# hdd-booster.net
KiCad netlist of a schematic drawn in EAGLE
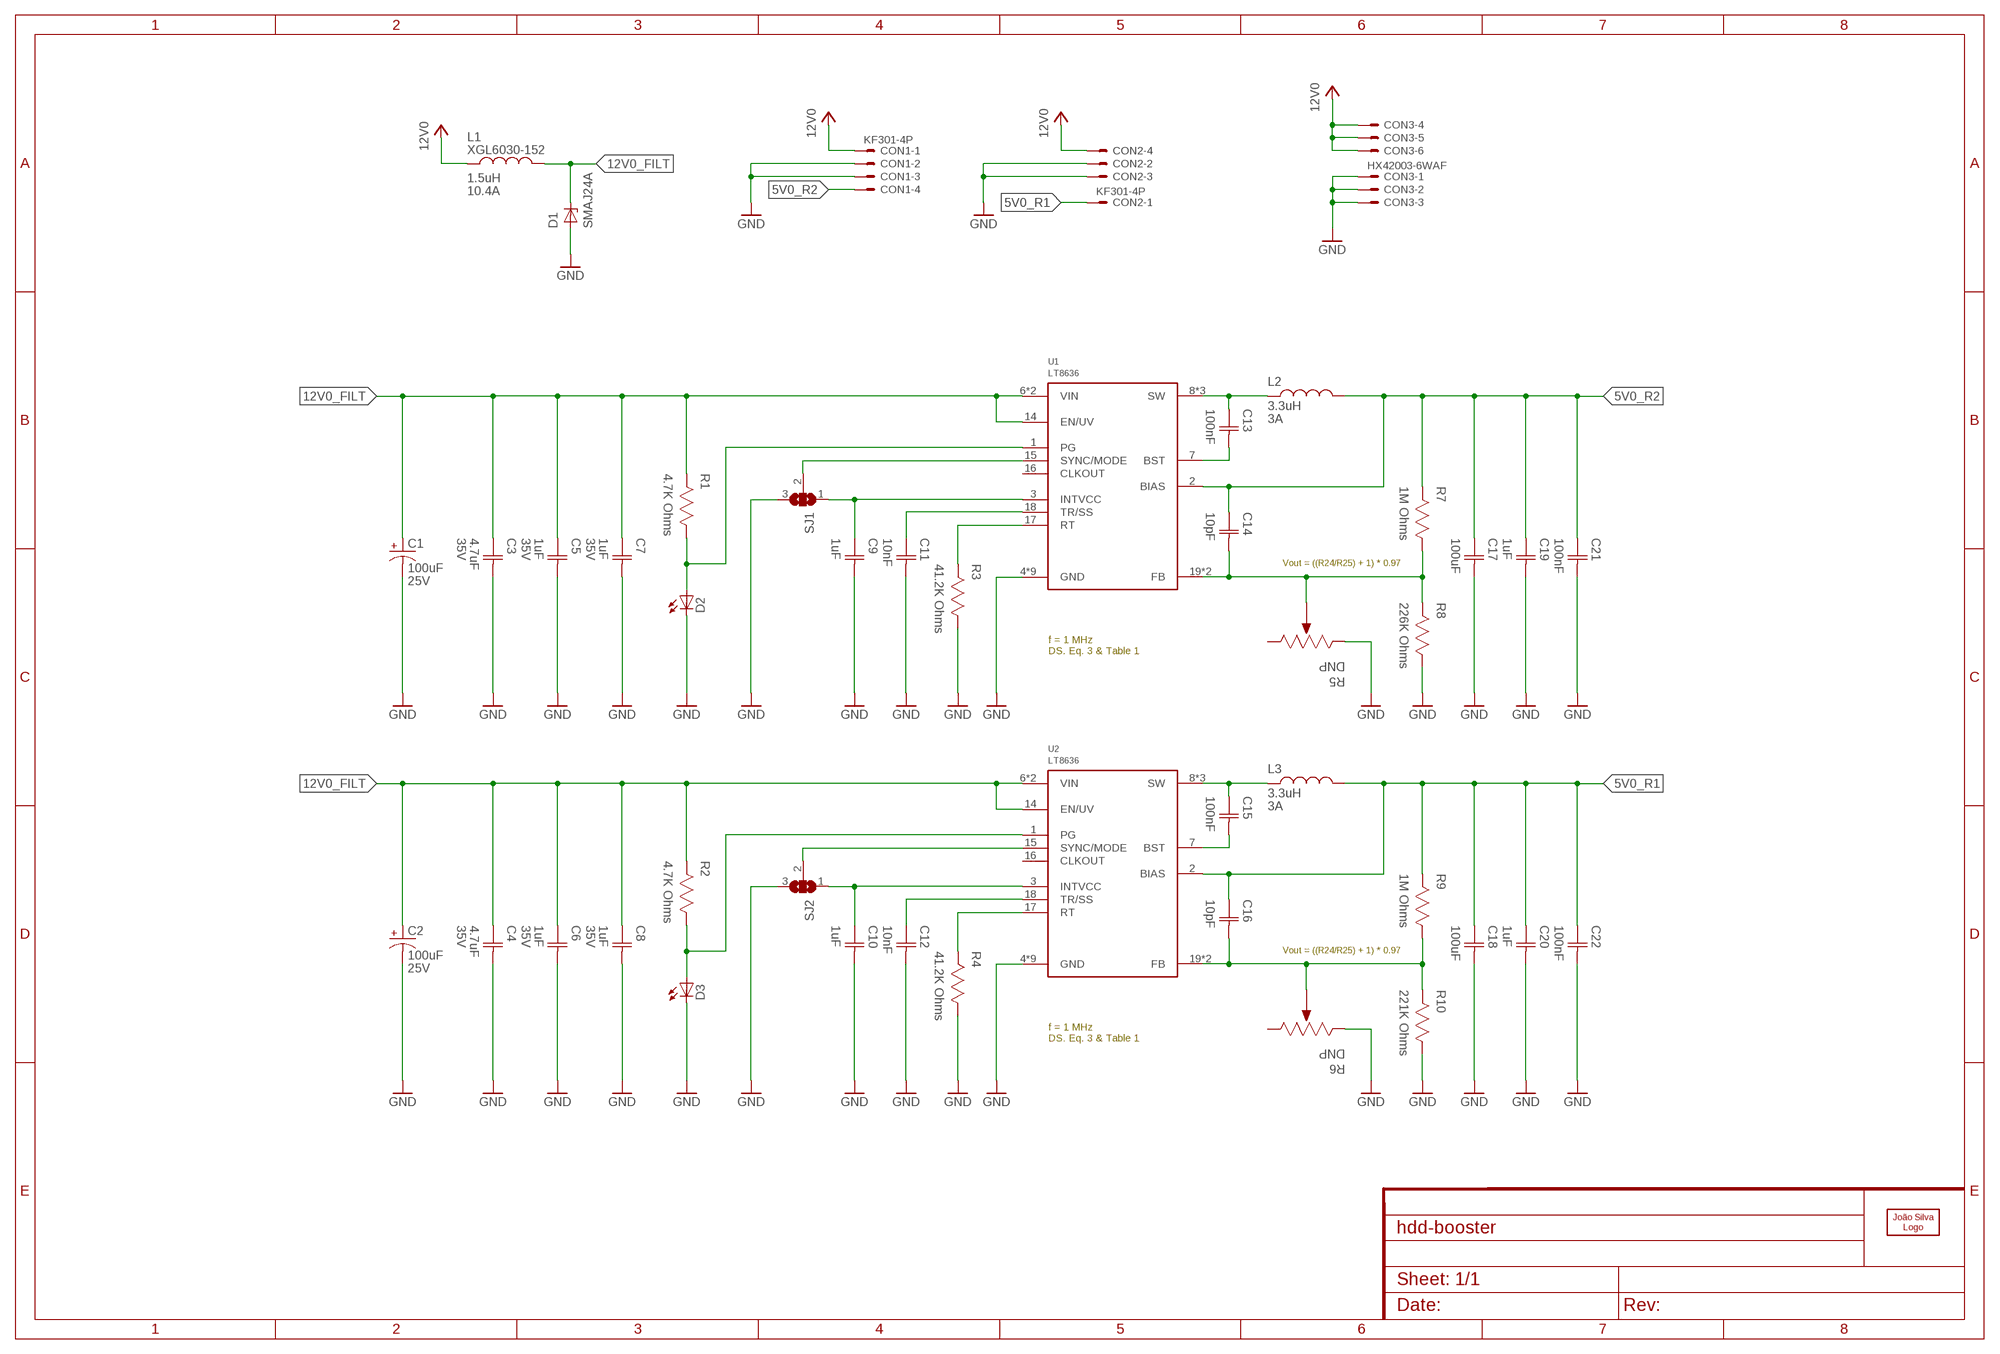
[diagram p0: schematic, sheet 1]

(export (version "E")
  (design (tool "Eeschema 10.0.6"))
  (components
    (comp (ref "C1")
      (value "100uF")
      (footprint "eagle-import:AL-CAP-CASE-D")
      (fields (field (name "VOLTAGE") "25V"))
      (libsource (lib "eagle-import") (part "ALUMINIUM-CAPACITOR-CASE-D"))
    )
    (comp (ref "C2")
      (value "100uF")
      (footprint "eagle-import:AL-CAP-CASE-D")
      (fields (field (name "VOLTAGE") "25V"))
      (libsource (lib "eagle-import") (part "ALUMINIUM-CAPACITOR-CASE-D"))
    )
    (comp (ref "C3")
      (value "4.7uF")
      (footprint "eagle-import:CAP0603")
      (fields (field (name "VOLTAGE") "35V"))
      (libsource (lib "eagle-import") (part "CAPACITOR-0603"))
    )
    (comp (ref "C4")
      (value "4.7uF")
      (footprint "eagle-import:CAP0603")
      (fields (field (name "VOLTAGE") "35V"))
      (libsource (lib "eagle-import") (part "CAPACITOR-0603"))
    )
    (comp (ref "C5")
      (value "1uF")
      (footprint "eagle-import:CAP0402")
      (fields (field (name "VOLTAGE") "35V"))
      (libsource (lib "eagle-import") (part "CAPACITOR-0402"))
    )
    (comp (ref "C6")
      (value "1uF")
      (footprint "eagle-import:CAP0402")
      (fields (field (name "VOLTAGE") "35V"))
      (libsource (lib "eagle-import") (part "CAPACITOR-0402"))
    )
    (comp (ref "C7")
      (value "1uF")
      (footprint "eagle-import:CAP0402")
      (fields (field (name "VOLTAGE") "35V"))
      (libsource (lib "eagle-import") (part "CAPACITOR-0402"))
    )
    (comp (ref "C8")
      (value "1uF")
      (footprint "eagle-import:CAP0402")
      (fields (field (name "VOLTAGE") "35V"))
      (libsource (lib "eagle-import") (part "CAPACITOR-0402"))
    )
    (comp (ref "C9")
      (value "1uF")
      (footprint "eagle-import:CAP0402")
      (libsource (lib "eagle-import") (part "CAPACITOR-0402"))
    )
    (comp (ref "C10")
      (value "1uF")
      (footprint "eagle-import:CAP0402")
      (libsource (lib "eagle-import") (part "CAPACITOR-0402"))
    )
    (comp (ref "C11")
      (value "10nF")
      (footprint "eagle-import:CAP0402")
      (libsource (lib "eagle-import") (part "CAPACITOR-0402"))
    )
    (comp (ref "C12")
      (value "10nF")
      (footprint "eagle-import:CAP0402")
      (libsource (lib "eagle-import") (part "CAPACITOR-0402"))
    )
    (comp (ref "C13")
      (value "100nF")
      (footprint "eagle-import:CAP0402")
      (libsource (lib "eagle-import") (part "CAPACITOR-0402"))
    )
    (comp (ref "C14")
      (value "10pF")
      (footprint "eagle-import:CAP0402")
      (libsource (lib "eagle-import") (part "CAPACITOR-0402"))
    )
    (comp (ref "C15")
      (value "100nF")
      (footprint "eagle-import:CAP0402")
      (libsource (lib "eagle-import") (part "CAPACITOR-0402"))
    )
    (comp (ref "C16")
      (value "10pF")
      (footprint "eagle-import:CAP0402")
      (libsource (lib "eagle-import") (part "CAPACITOR-0402"))
    )
    (comp (ref "C17")
      (value "100uF")
      (footprint "eagle-import:CAP1206")
      (libsource (lib "eagle-import") (part "CAPACITOR-1206"))
    )
    (comp (ref "C18")
      (value "100uF")
      (footprint "eagle-import:CAP1206")
      (libsource (lib "eagle-import") (part "CAPACITOR-1206"))
    )
    (comp (ref "C19")
      (value "1uF")
      (footprint "eagle-import:CAP0402")
      (libsource (lib "eagle-import") (part "CAPACITOR-0402"))
    )
    (comp (ref "C20")
      (value "1uF")
      (footprint "eagle-import:CAP0402")
      (libsource (lib "eagle-import") (part "CAPACITOR-0402"))
    )
    (comp (ref "C21")
      (value "100nF")
      (footprint "eagle-import:CAP0402")
      (libsource (lib "eagle-import") (part "CAPACITOR-0402"))
    )
    (comp (ref "C22")
      (value "100nF")
      (footprint "eagle-import:CAP0402")
      (libsource (lib "eagle-import") (part "CAPACITOR-0402"))
    )
    (comp (ref "CON1")
      (value "KF301-4P")
      (footprint "eagle-import:KF301-4P")
      (libsource (lib "eagle-import") (part "KF301-4P"))
    )
    (comp (ref "CON2")
      (value "KF301-4P")
      (footprint "eagle-import:KF301-4P")
      (libsource (lib "eagle-import") (part "KF301-4P"))
    )
    (comp (ref "CON3")
      (value "HX42003-6WAF")
      (footprint "eagle-import:HX42003-6WAF")
      (libsource (lib "eagle-import") (part "HX42003-6WAF"))
    )
    (comp (ref "D1")
      (value "SMAJ24A")
      (footprint "eagle-import:DO214AC")
      (fields (field (name "MF") "Littelfuse"))
      (libsource (lib "eagle-import") (part "SMAJA24"))
    )
    (comp (ref "D2")
      (value "LED1206")
      (footprint "eagle-import:1206")
      (libsource (lib "eagle-import") (part "LED1206"))
    )
    (comp (ref "D3")
      (value "LED1206")
      (footprint "eagle-import:1206")
      (libsource (lib "eagle-import") (part "LED1206"))
    )
    (comp (ref "L1")
      (value "1.5uH")
      (footprint "eagle-import:XGL6030")
      (fields (field (name "CURRENT") "10.4A") (field (name "REF") "XGL6030-152"))
      (libsource (lib "eagle-import") (part "XGL6030-152"))
    )
    (comp (ref "L2")
      (value "3.3uH")
      (footprint "eagle-import:XGL6030")
      (fields (field (name "CURRENT") "7.6A") (field (name "CURRENT_1") "3A"))
      (libsource (lib "eagle-import") (part "XGL6030-332"))
    )
    (comp (ref "L3")
      (value "3.3uH")
      (footprint "eagle-import:XGL6030")
      (fields (field (name "CURRENT") "7.6A") (field (name "CURRENT_1") "3A"))
      (libsource (lib "eagle-import") (part "XGL6030-332"))
    )
    (comp (ref "LOGO1")
      (value "JSILVA-5MM")
      (footprint "eagle-import:JSILVA_5MM")
      (libsource (lib "eagle-import") (part "JSILVA-5MM"))
    )
    (comp (ref "R1")
      (value "4.7K Ohms")
      (footprint "eagle-import:RES0402")
      (libsource (lib "eagle-import") (part "RESISTOR-0402"))
    )
    (comp (ref "R2")
      (value "4.7K Ohms")
      (footprint "eagle-import:RES0402")
      (libsource (lib "eagle-import") (part "RESISTOR-0402"))
    )
    (comp (ref "R3")
      (value "41.2K Ohms")
      (footprint "eagle-import:RES0402")
      (libsource (lib "eagle-import") (part "RESISTOR-0402"))
    )
    (comp (ref "R4")
      (value "41.2K Ohms")
      (footprint "eagle-import:RES0402")
      (libsource (lib "eagle-import") (part "RESISTOR-0402"))
    )
    (comp (ref "R5")
      (value "DNP")
      (footprint "eagle-import:POT3MM")
      (libsource (lib "eagle-import") (part "POTENTIOMETER-SMD-3X3"))
    )
    (comp (ref "R6")
      (value "DNP")
      (footprint "eagle-import:POT3MM")
      (libsource (lib "eagle-import") (part "POTENTIOMETER-SMD-3X3"))
    )
    (comp (ref "R7")
      (value "1M Ohms")
      (footprint "eagle-import:RES0402")
      (libsource (lib "eagle-import") (part "RESISTOR-0402"))
    )
    (comp (ref "R8")
      (value "226K Ohms")
      (footprint "eagle-import:RES0402")
      (libsource (lib "eagle-import") (part "RESISTOR-0402"))
    )
    (comp (ref "R9")
      (value "1M Ohms")
      (footprint "eagle-import:RES0402")
      (libsource (lib "eagle-import") (part "RESISTOR-0402"))
    )
    (comp (ref "R10")
      (value "221K Ohms")
      (footprint "eagle-import:RES0402")
      (libsource (lib "eagle-import") (part "RESISTOR-0402"))
    )
    (comp (ref "SJ1")
      (value "SJ2S")
      (footprint "eagle-import:SJ2_S")
      (libsource (lib "eagle-import") (part "SJ2S"))
    )
    (comp (ref "SJ2")
      (value "SJ2S")
      (footprint "eagle-import:SJ2_S")
      (libsource (lib "eagle-import") (part "SJ2S"))
    )
    (comp (ref "U1")
      (value "LT8636")
      (footprint "eagle-import:QFN20_ASYM_3X4_CORNER")
      (libsource (lib "eagle-import") (part "LT8636"))
    )
    (comp (ref "U2")
      (value "LT8636")
      (footprint "eagle-import:QFN20_ASYM_3X4_CORNER")
      (libsource (lib "eagle-import") (part "LT8636"))
    )
  )
  (nets
    (net (code "1") (name "5V0_R1") (class "Default")
      (node (ref "C16") (pin "1") (pinfunction "C1_1") (pintype "passive"))
      (node (ref "C18") (pin "1") (pinfunction "C1_1") (pintype "passive"))
      (node (ref "C20") (pin "1") (pinfunction "C1_1") (pintype "passive"))
      (node (ref "C22") (pin "1") (pinfunction "C1_1") (pintype "passive"))
      (node (ref "CON2") (pin "1") (pinfunction "S_1") (pintype "passive"))
      (node (ref "L3") (pin "2") (pinfunction "2_2") (pintype "passive"))
      (node (ref "R9") (pin "2") (pinfunction "2_2") (pintype "passive"))
      (node (ref "U2") (pin "2") (pinfunction "BIAS_2") (pintype "bidirectional"))
    )
    (net (code "2") (name "5V0_R2") (class "Default")
      (node (ref "C14") (pin "1") (pinfunction "C1_1") (pintype "passive"))
      (node (ref "C17") (pin "1") (pinfunction "C1_1") (pintype "passive"))
      (node (ref "C19") (pin "1") (pinfunction "C1_1") (pintype "passive"))
      (node (ref "C21") (pin "1") (pinfunction "C1_1") (pintype "passive"))
      (node (ref "CON1") (pin "4") (pinfunction "S_4") (pintype "passive"))
      (node (ref "L2") (pin "2") (pinfunction "2_2") (pintype "passive"))
      (node (ref "R7") (pin "2") (pinfunction "2_2") (pintype "passive"))
      (node (ref "U1") (pin "2") (pinfunction "BIAS_2") (pintype "bidirectional"))
    )
    (net (code "3") (name "12V0") (class "Default")
      (node (ref "CON1") (pin "1") (pinfunction "S_1") (pintype "passive"))
      (node (ref "CON2") (pin "4") (pinfunction "S_4") (pintype "passive"))
      (node (ref "CON3") (pin "4") (pinfunction "S_4") (pintype "passive"))
      (node (ref "CON3") (pin "5") (pinfunction "S_5") (pintype "passive"))
      (node (ref "CON3") (pin "6") (pinfunction "S_6") (pintype "passive"))
      (node (ref "L1") (pin "1") (pinfunction "1_1") (pintype "passive"))
    )
    (net (code "4") (name "12V0_FILT") (class "Default")
      (node (ref "C1") (pin "1") (pinfunction "+_1") (pintype "passive"))
      (node (ref "C2") (pin "1") (pinfunction "+_1") (pintype "passive"))
      (node (ref "C3") (pin "1") (pinfunction "C1_1") (pintype "passive"))
      (node (ref "C4") (pin "1") (pinfunction "C1_1") (pintype "passive"))
      (node (ref "C5") (pin "1") (pinfunction "C1_1") (pintype "passive"))
      (node (ref "C6") (pin "1") (pinfunction "C1_1") (pintype "passive"))
      (node (ref "C7") (pin "1") (pinfunction "C1_1") (pintype "passive"))
      (node (ref "C8") (pin "1") (pinfunction "C1_1") (pintype "passive"))
      (node (ref "D1") (pin "C") (pinfunction "C_C") (pintype "passive"))
      (node (ref "L1") (pin "2") (pinfunction "2_2") (pintype "passive"))
      (node (ref "R1") (pin "2") (pinfunction "2_2") (pintype "passive"))
      (node (ref "R2") (pin "2") (pinfunction "2_2") (pintype "passive"))
      (node (ref "U1") (pin "11") (pinfunction "VIN_11") (pintype "bidirectional"))
      (node (ref "U1") (pin "14") (pinfunction "EN/UV_14") (pintype "bidirectional"))
      (node (ref "U1") (pin "6") (pinfunction "VIN_6") (pintype "bidirectional"))
      (node (ref "U2") (pin "11") (pinfunction "VIN_11") (pintype "bidirectional"))
      (node (ref "U2") (pin "14") (pinfunction "EN/UV_14") (pintype "bidirectional"))
      (node (ref "U2") (pin "6") (pinfunction "VIN_6") (pintype "bidirectional"))
    )
    (net (code "5") (name "GND") (class "Default")
      (node (ref "C1") (pin "2") (pinfunction "-_2") (pintype "passive"))
      (node (ref "C10") (pin "2") (pinfunction "C2_2") (pintype "passive"))
      (node (ref "C11") (pin "2") (pinfunction "C2_2") (pintype "passive"))
      (node (ref "C12") (pin "2") (pinfunction "C2_2") (pintype "passive"))
      (node (ref "C17") (pin "2") (pinfunction "C2_2") (pintype "passive"))
      (node (ref "C18") (pin "2") (pinfunction "C2_2") (pintype "passive"))
      (node (ref "C19") (pin "2") (pinfunction "C2_2") (pintype "passive"))
      (node (ref "C2") (pin "2") (pinfunction "-_2") (pintype "passive"))
      (node (ref "C20") (pin "2") (pinfunction "C2_2") (pintype "passive"))
      (node (ref "C21") (pin "2") (pinfunction "C2_2") (pintype "passive"))
      (node (ref "C22") (pin "2") (pinfunction "C2_2") (pintype "passive"))
      (node (ref "C3") (pin "2") (pinfunction "C2_2") (pintype "passive"))
      (node (ref "C4") (pin "2") (pinfunction "C2_2") (pintype "passive"))
      (node (ref "C5") (pin "2") (pinfunction "C2_2") (pintype "passive"))
      (node (ref "C6") (pin "2") (pinfunction "C2_2") (pintype "passive"))
      (node (ref "C7") (pin "2") (pinfunction "C2_2") (pintype "passive"))
      (node (ref "C8") (pin "2") (pinfunction "C2_2") (pintype "passive"))
      (node (ref "C9") (pin "2") (pinfunction "C2_2") (pintype "passive"))
      (node (ref "CON1") (pin "2") (pinfunction "S_2") (pintype "passive"))
      (node (ref "CON1") (pin "3") (pinfunction "S_3") (pintype "passive"))
      (node (ref "CON2") (pin "2") (pinfunction "S_2") (pintype "passive"))
      (node (ref "CON2") (pin "3") (pinfunction "S_3") (pintype "passive"))
      (node (ref "CON3") (pin "1") (pinfunction "S_1") (pintype "passive"))
      (node (ref "CON3") (pin "2") (pinfunction "S_2") (pintype "passive"))
      (node (ref "CON3") (pin "3") (pinfunction "S_3") (pintype "passive"))
      (node (ref "D1") (pin "A") (pinfunction "A_A") (pintype "passive"))
      (node (ref "D2") (pin "C") (pinfunction "C_C") (pintype "passive"))
      (node (ref "D3") (pin "C") (pinfunction "C_C") (pintype "passive"))
      (node (ref "R10") (pin "1") (pinfunction "1_1") (pintype "passive"))
      (node (ref "R3") (pin "1") (pinfunction "1_1") (pintype "passive"))
      (node (ref "R4") (pin "1") (pinfunction "1_1") (pintype "passive"))
      (node (ref "R5") (pin "1") (pinfunction "CCW_1") (pintype "passive"))
      (node (ref "R6") (pin "1") (pinfunction "CCW_1") (pintype "passive"))
      (node (ref "R8") (pin "1") (pinfunction "1_1") (pintype "passive"))
      (node (ref "SJ1") (pin "3") (pinfunction "3_3") (pintype "passive"))
      (node (ref "SJ2") (pin "3") (pinfunction "3_3") (pintype "passive"))
      (node (ref "U1") (pin "12") (pinfunction "GND_12") (pintype "bidirectional"))
      (node (ref "U1") (pin "13") (pinfunction "GND_13") (pintype "bidirectional"))
      (node (ref "U1") (pin "21") (pinfunction "GND_21") (pintype "bidirectional"))
      (node (ref "U1") (pin "4") (pinfunction "GND_4") (pintype "bidirectional"))
      (node (ref "U1") (pin "5") (pinfunction "GND_5") (pintype "bidirectional"))
      (node (ref "U1") (pin "M1") (pinfunction "GND_M1") (pintype "bidirectional"))
      (node (ref "U1") (pin "M2") (pinfunction "GND_M2") (pintype "bidirectional"))
      (node (ref "U1") (pin "M3") (pinfunction "GND_M3") (pintype "bidirectional"))
      (node (ref "U1") (pin "M4") (pinfunction "GND_M4") (pintype "bidirectional"))
      (node (ref "U2") (pin "12") (pinfunction "GND_12") (pintype "bidirectional"))
      (node (ref "U2") (pin "13") (pinfunction "GND_13") (pintype "bidirectional"))
      (node (ref "U2") (pin "21") (pinfunction "GND_21") (pintype "bidirectional"))
      (node (ref "U2") (pin "4") (pinfunction "GND_4") (pintype "bidirectional"))
      (node (ref "U2") (pin "5") (pinfunction "GND_5") (pintype "bidirectional"))
      (node (ref "U2") (pin "M1") (pinfunction "GND_M1") (pintype "bidirectional"))
      (node (ref "U2") (pin "M2") (pinfunction "GND_M2") (pintype "bidirectional"))
      (node (ref "U2") (pin "M3") (pinfunction "GND_M3") (pintype "bidirectional"))
      (node (ref "U2") (pin "M4") (pinfunction "GND_M4") (pintype "bidirectional"))
    )
    (net (code "6") (name "Net-(C9-C1)") (class "Default")
      (node (ref "C9") (pin "1") (pinfunction "C1_1") (pintype "passive"))
      (node (ref "SJ1") (pin "1") (pinfunction "1_1") (pintype "passive"))
      (node (ref "U1") (pin "3") (pinfunction "INTVCC_3") (pintype "bidirectional"))
    )
    (net (code "7") (name "Net-(C10-C1)") (class "Default")
      (node (ref "C10") (pin "1") (pinfunction "C1_1") (pintype "passive"))
      (node (ref "SJ2") (pin "1") (pinfunction "1_1") (pintype "passive"))
      (node (ref "U2") (pin "3") (pinfunction "INTVCC_3") (pintype "bidirectional"))
    )
    (net (code "8") (name "Net-(C11-C1)") (class "Default")
      (node (ref "C11") (pin "1") (pinfunction "C1_1") (pintype "passive"))
      (node (ref "U1") (pin "18") (pinfunction "TR/SS_18") (pintype "bidirectional"))
    )
    (net (code "9") (name "Net-(C12-C1)") (class "Default")
      (node (ref "C12") (pin "1") (pinfunction "C1_1") (pintype "passive"))
      (node (ref "U2") (pin "18") (pinfunction "TR/SS_18") (pintype "bidirectional"))
    )
    (net (code "10") (name "Net-(C13-C1)") (class "Default")
      (node (ref "C13") (pin "1") (pinfunction "C1_1") (pintype "passive"))
      (node (ref "L2") (pin "1") (pinfunction "1_1") (pintype "passive"))
      (node (ref "U1") (pin "10") (pinfunction "SW_10") (pintype "bidirectional"))
      (node (ref "U1") (pin "8") (pinfunction "SW_8") (pintype "bidirectional"))
      (node (ref "U1") (pin "9") (pinfunction "SW_9") (pintype "bidirectional"))
    )
    (net (code "11") (name "Net-(C13-C2)") (class "Default")
      (node (ref "C13") (pin "2") (pinfunction "C2_2") (pintype "passive"))
      (node (ref "U1") (pin "7") (pinfunction "BST_7") (pintype "bidirectional"))
    )
    (net (code "12") (name "Net-(C14-C2)") (class "Default")
      (node (ref "C14") (pin "2") (pinfunction "C2_2") (pintype "passive"))
      (node (ref "R5") (pin "2") (pinfunction "WIPER_2") (pintype "passive"))
      (node (ref "R7") (pin "1") (pinfunction "1_1") (pintype "passive"))
      (node (ref "R8") (pin "2") (pinfunction "2_2") (pintype "passive"))
      (node (ref "U1") (pin "19") (pinfunction "FB_19") (pintype "bidirectional"))
      (node (ref "U1") (pin "20") (pinfunction "FB_20") (pintype "bidirectional"))
    )
    (net (code "13") (name "Net-(C15-C1)") (class "Default")
      (node (ref "C15") (pin "1") (pinfunction "C1_1") (pintype "passive"))
      (node (ref "L3") (pin "1") (pinfunction "1_1") (pintype "passive"))
      (node (ref "U2") (pin "10") (pinfunction "SW_10") (pintype "bidirectional"))
      (node (ref "U2") (pin "8") (pinfunction "SW_8") (pintype "bidirectional"))
      (node (ref "U2") (pin "9") (pinfunction "SW_9") (pintype "bidirectional"))
    )
    (net (code "14") (name "Net-(C15-C2)") (class "Default")
      (node (ref "C15") (pin "2") (pinfunction "C2_2") (pintype "passive"))
      (node (ref "U2") (pin "7") (pinfunction "BST_7") (pintype "bidirectional"))
    )
    (net (code "15") (name "Net-(C16-C2)") (class "Default")
      (node (ref "C16") (pin "2") (pinfunction "C2_2") (pintype "passive"))
      (node (ref "R10") (pin "2") (pinfunction "2_2") (pintype "passive"))
      (node (ref "R6") (pin "2") (pinfunction "WIPER_2") (pintype "passive"))
      (node (ref "R9") (pin "1") (pinfunction "1_1") (pintype "passive"))
      (node (ref "U2") (pin "19") (pinfunction "FB_19") (pintype "bidirectional"))
      (node (ref "U2") (pin "20") (pinfunction "FB_20") (pintype "bidirectional"))
    )
    (net (code "16") (name "Net-(U1-PG)") (class "Default")
      (node (ref "D2") (pin "A") (pinfunction "A_A") (pintype "passive"))
      (node (ref "R1") (pin "1") (pinfunction "1_1") (pintype "passive"))
      (node (ref "U1") (pin "1") (pinfunction "PG_1") (pintype "bidirectional"))
    )
    (net (code "17") (name "Net-(U1-RT)") (class "Default")
      (node (ref "R3") (pin "2") (pinfunction "2_2") (pintype "passive"))
      (node (ref "U1") (pin "17") (pinfunction "RT_17") (pintype "bidirectional"))
    )
    (net (code "18") (name "Net-(U1-SYNC{slash}MODE)") (class "Default")
      (node (ref "SJ1") (pin "2") (pinfunction "2_2") (pintype "passive"))
      (node (ref "U1") (pin "15") (pinfunction "SYNC/MODE_15") (pintype "bidirectional"))
    )
    (net (code "19") (name "Net-(U2-PG)") (class "Default")
      (node (ref "D3") (pin "A") (pinfunction "A_A") (pintype "passive"))
      (node (ref "R2") (pin "1") (pinfunction "1_1") (pintype "passive"))
      (node (ref "U2") (pin "1") (pinfunction "PG_1") (pintype "bidirectional"))
    )
    (net (code "20") (name "Net-(U2-RT)") (class "Default")
      (node (ref "R4") (pin "2") (pinfunction "2_2") (pintype "passive"))
      (node (ref "U2") (pin "17") (pinfunction "RT_17") (pintype "bidirectional"))
    )
    (net (code "21") (name "Net-(U2-SYNC{slash}MODE)") (class "Default")
      (node (ref "SJ2") (pin "2") (pinfunction "2_2") (pintype "passive"))
      (node (ref "U2") (pin "15") (pinfunction "SYNC/MODE_15") (pintype "bidirectional"))
    )
    (net (code "22") (name "unconnected-(R5-CW-Pad3)") (class "Default")
      (node (ref "R5") (pin "3") (pinfunction "CW_3") (pintype "passive"))
    )
    (net (code "23") (name "unconnected-(R6-CW-Pad3)") (class "Default")
      (node (ref "R6") (pin "3") (pinfunction "CW_3") (pintype "passive"))
    )
    (net (code "24") (name "unconnected-(U1-CLKOUT-Pad16)") (class "Default")
      (node (ref "U1") (pin "16") (pinfunction "CLKOUT_16") (pintype "bidirectional"))
    )
    (net (code "25") (name "unconnected-(U2-CLKOUT-Pad16)") (class "Default")
      (node (ref "U2") (pin "16") (pinfunction "CLKOUT_16") (pintype "bidirectional"))
    )
  )
)
